# Pithy_Pixel.net
KiCad netlist of a schematic drawn in EAGLE
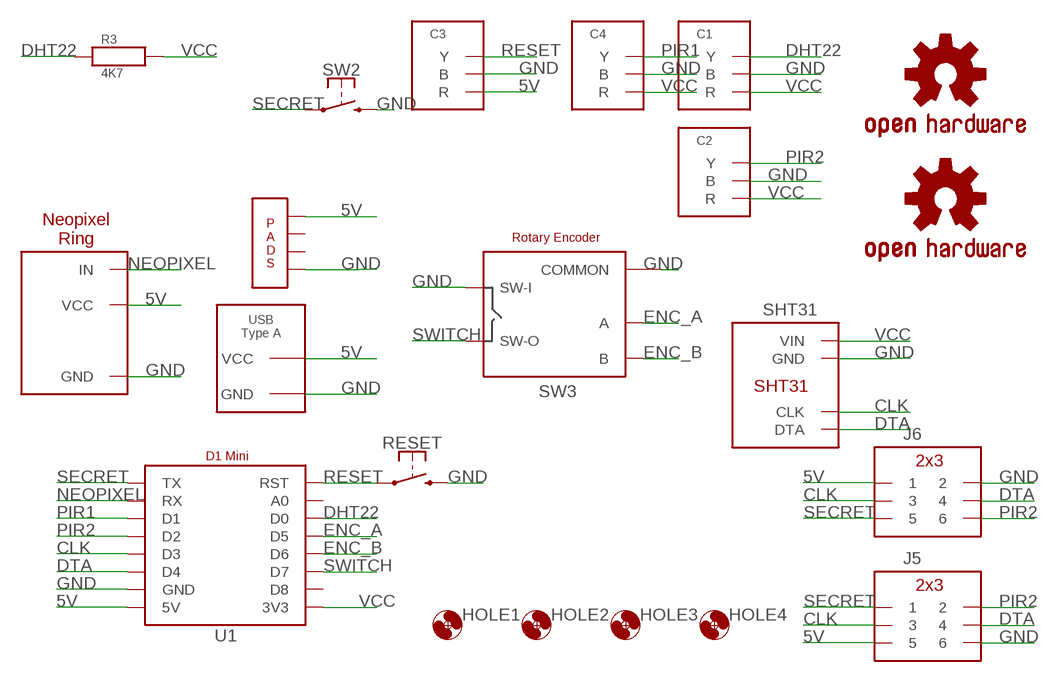
[diagram p0: schematic, sheet 1]

(export (version "E")
  (design (tool "Eeschema 10.0.6"))
  (components
    (comp (ref "C1")
      (value "JST_2MM_3PIN")
      (footprint "eagle-import:JST_2MM_3PIN")
      (libsource (lib "eagle-import") (part "JST_2MM_3PIN"))
    )
    (comp (ref "C2")
      (value "JST_2MM_3PIN")
      (footprint "eagle-import:JST_2MM_3PIN")
      (libsource (lib "eagle-import") (part "JST_2MM_3PIN"))
    )
    (comp (ref "C3")
      (value "JST_2MM_3PIN")
      (footprint "eagle-import:JST_2MM_3PIN")
      (libsource (lib "eagle-import") (part "JST_2MM_3PIN"))
    )
    (comp (ref "C4")
      (value "JST_2MM_3PIN")
      (footprint "eagle-import:JST_2MM_3PIN")
      (libsource (lib "eagle-import") (part "JST_2MM_3PIN"))
    )
    (comp (ref "HOLE1")
      (value "HOLE_3.2")
      (footprint "eagle-import:HOLE_3.2")
      (libsource (lib "eagle-import") (part "HOLE_3.2"))
    )
    (comp (ref "HOLE2")
      (value "HOLE_3.2")
      (footprint "eagle-import:HOLE_3.2")
      (libsource (lib "eagle-import") (part "HOLE_3.2"))
    )
    (comp (ref "HOLE3")
      (value "HOLE_3.2")
      (footprint "eagle-import:HOLE_3.2")
      (libsource (lib "eagle-import") (part "HOLE_3.2"))
    )
    (comp (ref "HOLE4")
      (value "HOLE_3.2")
      (footprint "eagle-import:HOLE_3.2")
      (libsource (lib "eagle-import") (part "HOLE_3.2"))
    )
    (comp (ref "IC1")
      (value "NEOPIXEL_RING_NO_OUT")
      (footprint "eagle-import:NEOPIXEL_RING_SMALL_NO_OUT")
      (libsource (lib "eagle-import") (part "NEOPIXEL_RING_NO_OUT"))
    )
    (comp (ref "J5")
      (value "DIL_2X03FEMALE")
      (footprint "eagle-import:2X3-RAF")
      (libsource (lib "eagle-import") (part "DIL_2X03FEMALE"))
    )
    (comp (ref "J6")
      (value "DIL_2X03FEMALE")
      (footprint "eagle-import:2X3-RAF")
      (libsource (lib "eagle-import") (part "DIL_2X03FEMALE"))
    )
    (comp (ref "LOGO1")
      (value "OSHW-LOGOM")
      (footprint "eagle-import:OSHW-LOGO-M")
      (libsource (lib "eagle-import") (part "OSHW-LOGOM"))
    )
    (comp (ref "LOGO2")
      (value "OSHW-LOGOS")
      (footprint "eagle-import:OSHW-LOGO-S")
      (libsource (lib "eagle-import") (part "OSHW-LOGOS"))
    )
    (comp (ref "R3")
      (value "4K7")
      (footprint "eagle-import:1_4W_RESISTOR")
      (libsource (lib "eagle-import") (part "1/4W_RESISTOR"))
    )
    (comp (ref "RESET")
      (value "SPDT_MOMENTARY")
      (footprint "eagle-import:SPDT_RIGHT_ANGLE")
      (libsource (lib "eagle-import") (part "SPDT_MOMENTARY"))
    )
    (comp (ref "SHT31")
      (value "SHT31RIGHT_ANGLED")
      (footprint "eagle-import:SHT31_RIGHT_ANGLE")
      (libsource (lib "eagle-import") (part "SHT31RIGHT_ANGLED"))
    )
    (comp (ref "SW2")
      (value "SPDT_MOMENTARY")
      (footprint "eagle-import:SPDT_RIGHT_ANGLE")
      (libsource (lib "eagle-import") (part "SPDT_MOMENTARY"))
    )
    (comp (ref "SW3")
      (value "ENCODER")
      (footprint "eagle-import:ROTARY_ENCODER")
      (libsource (lib "eagle-import") (part "ROTARY_ENCODER"))
    )
    (comp (ref "U$1")
      (value "USB_TYPE_A")
      (footprint "eagle-import:USB_TYPE_A_BACKWARDS")
      (libsource (lib "eagle-import") (part "USB_TYPE_A"))
    )
    (comp (ref "U$2")
      (value "PADS_4")
      (footprint "eagle-import:PADS_4")
      (libsource (lib "eagle-import") (part "PADS_4"))
    )
    (comp (ref "U1")
      (value "D1_MINI")
      (footprint "eagle-import:D1_MINI")
      (libsource (lib "eagle-import") (part "D1_MINI"))
    )
  )
  (nets
    (net (code "1") (name "/5V") (class "Default")
      (node (ref "C3") (pin "RED") (pinfunction "R_RED") (pintype "bidirectional"))
      (node (ref "IC1") (pin "VCC@1") (pinfunction "VCC_VCC@1") (pintype "bidirectional"))
      (node (ref "J5") (pin "5") (pinfunction "5_5") (pintype "bidirectional"))
      (node (ref "J6") (pin "1") (pinfunction "1_1") (pintype "bidirectional"))
      (node (ref "U$1") (pin "VCC") (pinfunction "VCC_VCC") (pintype "bidirectional"))
      (node (ref "U$2") (pin "P$4") (pinfunction "P$4_P$4") (pintype "bidirectional"))
      (node (ref "U1") (pin "5V") (pinfunction "5V_5V") (pintype "bidirectional"))
    )
    (net (code "2") (name "/CLK") (class "Default")
      (node (ref "J5") (pin "3") (pinfunction "3_3") (pintype "bidirectional"))
      (node (ref "J6") (pin "3") (pinfunction "3_3") (pintype "bidirectional"))
      (node (ref "SHT31") (pin "CLK") (pinfunction "CLK_CLK") (pintype "bidirectional"))
      (node (ref "U1") (pin "D3") (pinfunction "D3_D3") (pintype "bidirectional"))
    )
    (net (code "3") (name "/DHT22") (class "Default")
      (node (ref "C1") (pin "YELLOW") (pinfunction "Y_YELLOW") (pintype "bidirectional"))
      (node (ref "R3") (pin "P$1") (pinfunction "P$1_P$1") (pintype "passive"))
      (node (ref "U1") (pin "D0") (pinfunction "D0_D0") (pintype "bidirectional"))
    )
    (net (code "4") (name "/DTA") (class "Default")
      (node (ref "J5") (pin "4") (pinfunction "4_4") (pintype "bidirectional"))
      (node (ref "J6") (pin "4") (pinfunction "4_4") (pintype "bidirectional"))
      (node (ref "SHT31") (pin "DTA") (pinfunction "DTA_DTA") (pintype "bidirectional"))
      (node (ref "U1") (pin "D4") (pinfunction "D4_D4") (pintype "bidirectional"))
    )
    (net (code "5") (name "/ENC_A") (class "Default")
      (node (ref "SW3") (pin "A") (pinfunction "A_A") (pintype "output"))
      (node (ref "U1") (pin "D5") (pinfunction "D5_D5") (pintype "bidirectional"))
    )
    (net (code "6") (name "/ENC_B") (class "Default")
      (node (ref "SW3") (pin "B") (pinfunction "B_B") (pintype "output"))
      (node (ref "U1") (pin "D6") (pinfunction "D6_D6") (pintype "bidirectional"))
    )
    (net (code "7") (name "/GND") (class "Default")
      (node (ref "C1") (pin "BLACK") (pinfunction "B_BLACK") (pintype "bidirectional"))
      (node (ref "C2") (pin "BLACK") (pinfunction "B_BLACK") (pintype "bidirectional"))
      (node (ref "C3") (pin "BLACK") (pinfunction "B_BLACK") (pintype "bidirectional"))
      (node (ref "C4") (pin "BLACK") (pinfunction "B_BLACK") (pintype "bidirectional"))
      (node (ref "IC1") (pin "GND@2") (pinfunction "GND_GND@2") (pintype "bidirectional"))
      (node (ref "J5") (pin "6") (pinfunction "6_6") (pintype "bidirectional"))
      (node (ref "J6") (pin "2") (pinfunction "2_2") (pintype "bidirectional"))
      (node (ref "RESET") (pin "2") (pinfunction "3_2") (pintype "passive"))
      (node (ref "SHT31") (pin "GND") (pinfunction "GND_GND") (pintype "bidirectional"))
      (node (ref "SW2") (pin "2") (pinfunction "3_2") (pintype "passive"))
      (node (ref "SW3") (pin "C") (pinfunction "COMMON_C") (pintype "input"))
      (node (ref "SW3") (pin "SW+") (pinfunction "SW-I_SW+") (pintype "input"))
      (node (ref "U$1") (pin "GND") (pinfunction "GND_GND") (pintype "bidirectional"))
      (node (ref "U$2") (pin "P$1") (pinfunction "P$1_P$1") (pintype "bidirectional"))
      (node (ref "U1") (pin "GND") (pinfunction "GND_GND") (pintype "bidirectional"))
    )
    (net (code "8") (name "/NEOPIXEL") (class "Default")
      (node (ref "IC1") (pin "IN") (pinfunction "IN_IN") (pintype "bidirectional"))
      (node (ref "U1") (pin "RX") (pinfunction "RX_RX") (pintype "bidirectional"))
    )
    (net (code "9") (name "/PIR1") (class "Default")
      (node (ref "C4") (pin "YELLOW") (pinfunction "Y_YELLOW") (pintype "bidirectional"))
      (node (ref "U1") (pin "D1") (pinfunction "D1_D1") (pintype "bidirectional"))
    )
    (net (code "10") (name "/PIR2") (class "Default")
      (node (ref "C2") (pin "YELLOW") (pinfunction "Y_YELLOW") (pintype "bidirectional"))
      (node (ref "J5") (pin "2") (pinfunction "2_2") (pintype "bidirectional"))
      (node (ref "J6") (pin "6") (pinfunction "6_6") (pintype "bidirectional"))
      (node (ref "U1") (pin "D2") (pinfunction "D2_D2") (pintype "bidirectional"))
    )
    (net (code "11") (name "/RESET") (class "Default")
      (node (ref "C3") (pin "YELLOW") (pinfunction "Y_YELLOW") (pintype "bidirectional"))
      (node (ref "RESET") (pin "1") (pinfunction "1_1") (pintype "passive"))
      (node (ref "U1") (pin "RST") (pinfunction "RST_RST") (pintype "bidirectional"))
    )
    (net (code "12") (name "/SECRET") (class "Default")
      (node (ref "J5") (pin "1") (pinfunction "1_1") (pintype "bidirectional"))
      (node (ref "J6") (pin "5") (pinfunction "5_5") (pintype "bidirectional"))
      (node (ref "SW2") (pin "1") (pinfunction "1_1") (pintype "passive"))
      (node (ref "U1") (pin "TX") (pinfunction "TX_TX") (pintype "bidirectional"))
    )
    (net (code "13") (name "/SWITCH") (class "Default")
      (node (ref "SW3") (pin "SW-") (pinfunction "SW-O_SW-") (pintype "output"))
      (node (ref "U1") (pin "D7") (pinfunction "D7_D7") (pintype "bidirectional"))
    )
    (net (code "14") (name "/VCC") (class "Default")
      (node (ref "C1") (pin "RED") (pinfunction "R_RED") (pintype "bidirectional"))
      (node (ref "C2") (pin "RED") (pinfunction "R_RED") (pintype "bidirectional"))
      (node (ref "C4") (pin "RED") (pinfunction "R_RED") (pintype "bidirectional"))
      (node (ref "R3") (pin "P$2") (pinfunction "P$2_P$2") (pintype "passive"))
      (node (ref "SHT31") (pin "VIN") (pinfunction "VIN_VIN") (pintype "bidirectional"))
      (node (ref "U1") (pin "3V3") (pinfunction "3V3_3V3") (pintype "bidirectional"))
    )
    (net (code "15") (name "unconnected-(U$2-PadP$2)") (class "Default")
      (node (ref "U$2") (pin "P$2") (pinfunction "P$2_P$2") (pintype "bidirectional"))
    )
    (net (code "16") (name "unconnected-(U$2-PadP$3)") (class "Default")
      (node (ref "U$2") (pin "P$3") (pinfunction "P$3_P$3") (pintype "bidirectional"))
    )
    (net (code "17") (name "unconnected-(U1-PadA0)") (class "Default")
      (node (ref "U1") (pin "A0") (pinfunction "A0_A0") (pintype "bidirectional"))
    )
    (net (code "18") (name "unconnected-(U1-PadD8)") (class "Default")
      (node (ref "U1") (pin "D8") (pinfunction "D8_D8") (pintype "bidirectional"))
    )
  )
)
